# HA_Power.net
KiCad netlist of a schematic drawn in Altium Designer
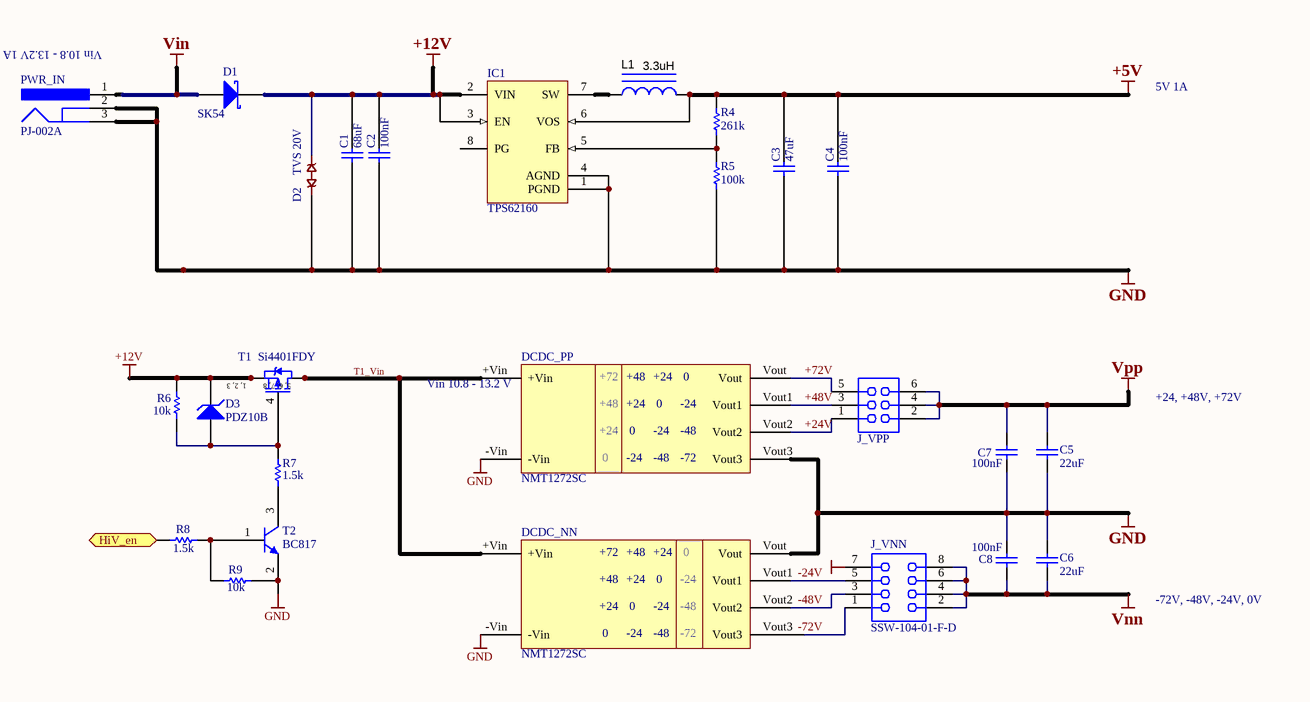
[diagram p0: HA_Power.SchDoc]

(export (version "E")
  (design (tool "Eeschema 10.0.6"))
  (components
    (comp (ref "C1")
      (value "68uF")
      (footprint "MURA-GRM-55D_V")
      (fields (field (name "MPN") "KRM55WR71E686MH01L") (field (name "MANUFACTURER") "Murata"))
      (libsource (lib "Altium Content Vault") (part "CMP-0817-00001-1"))
    )
    (comp (ref "C2")
      (value "100nF")
      (footprint "CAPC0805(2012)75_N")
      (fields (field (name "TOLERANCE") "±10%"))
      (libsource (lib "Altium Content Vault") (part "CMP-1036-00417-1"))
    )
    (comp (ref "C3")
      (value "47uF")
      (footprint "CAPC0805(2012)75_N")
      (fields (field (name "TOLERANCE") "±10%") (field (name "PARTNUMBER") "GRM21BR61A476ME15L"))
      (libsource (lib "Altium Content Vault") (part "CMP-1036-00417-1"))
    )
    (comp (ref "C4")
      (value "100nF")
      (footprint "CAPC0805(2012)75_N")
      (fields (field (name "TOLERANCE") "±10%"))
      (libsource (lib "Altium Content Vault") (part "CMP-1036-00417-1"))
    )
    (comp (ref "C5")
      (value "22uF")
      (footprint "MURA-GRM-55D_V")
      (fields (field (name "MPN") "KRM55WR72A226MH01L") (field (name "MANUFACTURER") "Murata"))
      (libsource (lib "Altium Content Vault") (part "CMP-0817-00001-1"))
    )
    (comp (ref "C6")
      (value "22uF")
      (footprint "MURA-GRM-55D_V")
      (fields (field (name "MPN") "KRM55WR72A226MH01L") (field (name "MANUFACTURER") "Murata"))
      (libsource (lib "Altium Content Vault") (part "CMP-0817-00001-1"))
    )
    (comp (ref "C7")
      (value "100nF")
      (footprint "CAPC0805(2012)75_N")
      (fields (field (name "TOLERANCE") "±10%"))
      (libsource (lib "Altium Content Vault") (part "CMP-1036-00417-1"))
    )
    (comp (ref "C8")
      (value "100nF")
      (footprint "CAPC0805(2012)75_N")
      (fields (field (name "TOLERANCE") "±10%"))
      (libsource (lib "Altium Content Vault") (part "CMP-1036-00417-1"))
    )
    (comp (ref "D1")
      (value "SK54")
      (footprint "VISH-DO-214AC-2_V")
      (fields (field (name "MANUFACTURER") "Micro commercial co") (field (name "MPN") "SK54A-LTP"))
      (libsource (lib "Altium Content Vault") (part "CMP-0549-00004-1"))
    )
    (comp (ref "D2")
      (value "TVS 20V")
      (footprint "DO214AC_BIDIR")
      (fields (field (name "MANUFACTURER") "Bourns") (field (name "MPN") "SMAJ20CA"))
      (libsource (lib "mms") (part "DIODE_BIDIR-DO214AC"))
    )
    (comp (ref "D3")
      (value "PDZ10B")
      (footprint "NXP-SOD323_V")
      (description "Zener diode")
      (fields (field (name "MANUFACTURER") "NXP"))
      (libsource (lib "Altium Content Vault") (part "CMP-2000-06888-1"))
    )
    (comp (ref "DCDC_NN")
      (value "NMT1272SC")
      (footprint "NMT1272SC")
      (fields (field (name "MANUFACTURER") "Murata"))
      (libsource (lib "Lib_murata") (part "NMT1272SC"))
    )
    (comp (ref "DCDC_PP")
      (value "NMT1272SC")
      (footprint "NMT1272SC")
      (fields (field (name "MANUFACTURER") "Murata"))
      (libsource (lib "Lib_murata") (part "NMT1272SC"))
    )
    (comp (ref "IC1")
      (value "TPS62160")
      (footprint "DGK8_N")
      (fields (field (name "MANUFACTURER") "Texas Instruments") (field (name "MPN") "TPS62160DGKR"))
      (libsource (lib "Altium Content Vault") (part "CMP-0323-00440-1"))
    )
    (comp (ref "J_VNN")
      (value "SSW-104-01-F-D")
      (footprint "SMTC-SSW-104-01-X-D")
      (description "SQ Post Socket, Through-hole, Vertical, -55 to 125 degC, 2.54mm Pitch, 8-Pin, Female, RoHS")
      (fields (field (name "MANUFACTURER") "Samtec"))
      (libsource (lib "Altium Content Vault") (part "CMP-1023-00336-1"))
    )
    (comp (ref "J_VPP")
      (value "SSW-103-01-F-D")
      (footprint "SMTC-SSW-103-01-X-D")
      (description "SQ Post Socket, Through-hole, Vertical, -55 to 125 degC, 2.54 mm Pitch, 6-Pin, Female, RoHS")
      (fields (field (name "MANUFACTURER") "Samtec"))
      (libsource (lib "Altium Content Vault") (part "CMP-1023-00329-1"))
    )
    (comp (ref "L1")
      (value "3.3uH")
      (footprint "XPL2010")
      (description "XPL2010 Inductor")
      (fields (field (name "MPN") "XPL2010-332MLB") (field (name "MANUFACTURER") "Coilcraft"))
      (libsource (lib "Inductor_Coilcraft") (part "XPL2010-332MLB"))
    )
    (comp (ref "PWR_IN")
      (value "PJ-002A")
      (footprint "CUI-PJ-002A_V")
      (fields (field (name "MANUFACTURER") "CUIInc."))
      (libsource (lib "Altium Content Vault") (part "CMP-2000-06895-1"))
    )
    (comp (ref "R4")
      (value "261k")
      (footprint "RESC0805(2012)_L")
      (description "0.125W 1% 0805 (2012 Metric)  SMD")
      (fields (field (name "POWER") "0.125 W") (field (name "TOLERANCE") "1 %"))
      (libsource (lib "Altium Content Vault") (part "CMP-1013-00429-1"))
    )
    (comp (ref "R5")
      (value "100k")
      (footprint "RESC0805(2012)_L")
      (description "0.125W 1% 0805 (2012 Metric)  SMD")
      (fields (field (name "POWER") "0.125 W") (field (name "TOLERANCE") "1 %"))
      (libsource (lib "Altium Content Vault") (part "CMP-1013-00429-1"))
    )
    (comp (ref "R6")
      (value "10k")
      (footprint "RESC0805(2012)_L")
      (description "0.125W 1% 0805 (2012 Metric)  SMD")
      (fields (field (name "POWER") "0.125 W") (field (name "TOLERANCE") "1 %"))
      (libsource (lib "Altium Content Vault") (part "CMP-1013-00429-1"))
    )
    (comp (ref "R7")
      (value "1.5k")
      (footprint "RESC0805(2012)_L")
      (description "0.125W 1% 0805 (2012 Metric)  SMD")
      (fields (field (name "POWER") "0.125 W") (field (name "TOLERANCE") "1 %"))
      (libsource (lib "Altium Content Vault") (part "CMP-1013-00429-1"))
    )
    (comp (ref "R8")
      (value "1.5k")
      (footprint "RESC0805(2012)_L")
      (description "0.125W 1% 0805 (2012 Metric)  SMD")
      (fields (field (name "POWER") "0.125 W") (field (name "TOLERANCE") "1 %"))
      (libsource (lib "Altium Content Vault") (part "CMP-1013-00429-1"))
    )
    (comp (ref "R9")
      (value "10k")
      (footprint "RESC0805(2012)_L")
      (description "0.125W 1% 0805 (2012 Metric)  SMD")
      (fields (field (name "POWER") "0.125 W") (field (name "TOLERANCE") "1 %"))
      (libsource (lib "Altium Content Vault") (part "CMP-1013-00429-1"))
    )
    (comp (ref "T1")
      (value "Si4401FDY")
      (footprint "SO08")
      (description "HEXFET Power MOSFET")
      (libsource (lib "fb") (part "P-MOSFET2"))
    )
    (comp (ref "T2")
      (value "BC817")
      (footprint "DIOD-SOT323-3_V")
      (description "NPN Small Signal Transistor, 45 V, 500 mA")
      (fields (field (name "MANUFACTURER") "DiodesIncorporated") (field (name "MPN") "BC817-40W-7"))
      (libsource (lib "Altium Content Vault") (part "CMP-2000-05934-1"))
    )
  )
  (nets
    (net (code "1") (name "+5V") (class "Default")
      (node (ref "C3") (pin "2") (pinfunction "2_2") (pintype "passive"))
      (node (ref "C4") (pin "2") (pinfunction "2_2") (pintype "passive"))
      (node (ref "IC1") (pin "6") (pinfunction "VOS_6") (pintype "input"))
      (node (ref "L1") (pin "2") (pinfunction "2_2") (pintype "passive"))
      (node (ref "R4") (pin "1") (pinfunction "1_1") (pintype "passive"))
    )
    (net (code "2") (name "+12V") (class "Default")
      (node (ref "C1") (pin "2") (pinfunction "2_2") (pintype "passive"))
      (node (ref "C2") (pin "2") (pinfunction "2_2") (pintype "passive"))
      (node (ref "D1") (pin "2") (pinfunction "K_2") (pintype "passive"))
      (node (ref "D2") (pin "2") (pinfunction "2_2") (pintype "passive"))
      (node (ref "D3") (pin "2") (pinfunction "K_2") (pintype "passive"))
      (node (ref "IC1") (pin "2") (pinfunction "VIN_2") (pintype "power_in"))
      (node (ref "IC1") (pin "3") (pinfunction "EN_3") (pintype "input"))
      (node (ref "R6") (pin "1") (pinfunction "1_1") (pintype "passive"))
      (node (ref "T1") (pin "1") (pinfunction "S_1") (pintype "passive"))
      (node (ref "T1") (pin "2") (pinfunction "S_2") (pintype "passive"))
      (node (ref "T1") (pin "3") (pinfunction "S_3") (pintype "passive"))
    )
    (net (code "3") (name "/+24V") (class "Default")
      (node (ref "DCDC_PP") (pin "Vout2") (pinfunction "Vout2_Vout2") (pintype "passive"))
      (node (ref "J_VPP") (pin "1") (pinfunction "1_1") (pintype "passive"))
    )
    (net (code "4") (name "/+48V") (class "Default")
      (node (ref "DCDC_PP") (pin "Vout1") (pinfunction "Vout1_Vout1") (pintype "passive"))
      (node (ref "J_VPP") (pin "3") (pinfunction "3_3") (pintype "passive"))
    )
    (net (code "5") (name "/+72V") (class "Default")
      (node (ref "DCDC_PP") (pin "Vout") (pinfunction "Vout_Vout") (pintype "passive"))
      (node (ref "J_VPP") (pin "5") (pinfunction "5_5") (pintype "passive"))
    )
    (net (code "6") (name "/-24V") (class "Default")
      (node (ref "DCDC_NN") (pin "Vout1") (pinfunction "Vout1_Vout1") (pintype "passive"))
      (node (ref "J_VNN") (pin "5") (pinfunction "5_5") (pintype "passive"))
    )
    (net (code "7") (name "/-48V") (class "Default")
      (node (ref "DCDC_NN") (pin "Vout2") (pinfunction "Vout2_Vout2") (pintype "passive"))
      (node (ref "J_VNN") (pin "3") (pinfunction "3_3") (pintype "passive"))
    )
    (net (code "8") (name "/-72V") (class "Default")
      (node (ref "DCDC_NN") (pin "Vout3") (pinfunction "Vout3_Vout3") (pintype "passive"))
      (node (ref "J_VNN") (pin "1") (pinfunction "1_1") (pintype "passive"))
    )
    (net (code "9") (name "/HiV_en") (class "Default")
      (node (ref "R8") (pin "2") (pinfunction "2_2") (pintype "passive"))
    )
    (net (code "10") (name "/T1_Vin") (class "Default")
      (node (ref "DCDC_NN") (pin "+Vin") (pinfunction "+Vin_+Vin") (pintype "power_in"))
      (node (ref "DCDC_PP") (pin "+Vin") (pinfunction "+Vin_+Vin") (pintype "power_in"))
      (node (ref "T1") (pin "5") (pinfunction "D_5") (pintype "passive"))
      (node (ref "T1") (pin "6") (pinfunction "D_6") (pintype "passive"))
      (node (ref "T1") (pin "7") (pinfunction "D_7") (pintype "passive"))
      (node (ref "T1") (pin "8") (pinfunction "D_8") (pintype "passive"))
    )
    (net (code "11") (name "GND") (class "Default")
      (node (ref "C1") (pin "1") (pinfunction "1_1") (pintype "passive"))
      (node (ref "C2") (pin "1") (pinfunction "1_1") (pintype "passive"))
      (node (ref "C3") (pin "1") (pinfunction "1_1") (pintype "passive"))
      (node (ref "C4") (pin "1") (pinfunction "1_1") (pintype "passive"))
      (node (ref "C5") (pin "1") (pinfunction "1_1") (pintype "passive"))
      (node (ref "C6") (pin "2") (pinfunction "2_2") (pintype "passive"))
      (node (ref "C7") (pin "1") (pinfunction "1_1") (pintype "passive"))
      (node (ref "C8") (pin "2") (pinfunction "2_2") (pintype "passive"))
      (node (ref "D2") (pin "1") (pinfunction "1_1") (pintype "passive"))
      (node (ref "DCDC_NN") (pin "-Vin") (pinfunction "-Vin_-Vin") (pintype "passive"))
      (node (ref "DCDC_NN") (pin "Vout") (pinfunction "Vout_Vout") (pintype "passive"))
      (node (ref "DCDC_PP") (pin "-Vin") (pinfunction "-Vin_-Vin") (pintype "passive"))
      (node (ref "DCDC_PP") (pin "Vout3") (pinfunction "Vout3_Vout3") (pintype "passive"))
      (node (ref "IC1") (pin "1") (pinfunction "PGND_1") (pintype "power_in"))
      (node (ref "IC1") (pin "4") (pinfunction "AGND_4") (pintype "power_in"))
      (node (ref "J_VNN") (pin "7") (pinfunction "7_7") (pintype "passive"))
      (node (ref "PWR_IN") (pin "2") (pinfunction "2_2") (pintype "passive"))
      (node (ref "PWR_IN") (pin "3") (pinfunction "3_3") (pintype "passive"))
      (node (ref "R5") (pin "2") (pinfunction "2_2") (pintype "passive"))
      (node (ref "R9") (pin "1") (pinfunction "1_1") (pintype "passive"))
      (node (ref "T2") (pin "2") (pinfunction "E_2") (pintype "passive"))
    )
    (net (code "12") (name "Net-(D3-A)") (class "Default")
      (node (ref "D3") (pin "1") (pinfunction "A_1") (pintype "passive"))
      (node (ref "R6") (pin "2") (pinfunction "2_2") (pintype "passive"))
      (node (ref "R7") (pin "2") (pinfunction "2_2") (pintype "passive"))
      (node (ref "T1") (pin "4") (pinfunction "G_4") (pintype "passive"))
    )
    (net (code "13") (name "Net-(IC1-FB)") (class "Default")
      (node (ref "IC1") (pin "5") (pinfunction "FB_5") (pintype "input"))
      (node (ref "R4") (pin "2") (pinfunction "2_2") (pintype "passive"))
      (node (ref "R5") (pin "1") (pinfunction "1_1") (pintype "passive"))
    )
    (net (code "14") (name "Net-(IC1-SW)") (class "Default")
      (node (ref "IC1") (pin "7") (pinfunction "SW_7") (pintype "power_in"))
      (node (ref "L1") (pin "1") (pinfunction "1_1") (pintype "passive"))
    )
    (net (code "15") (name "Net-(T2-B)") (class "Default")
      (node (ref "R8") (pin "1") (pinfunction "1_1") (pintype "passive"))
      (node (ref "R9") (pin "2") (pinfunction "2_2") (pintype "passive"))
      (node (ref "T2") (pin "1") (pinfunction "B_1") (pintype "passive"))
    )
    (net (code "16") (name "Net-(T2-C)") (class "Default")
      (node (ref "R7") (pin "1") (pinfunction "1_1") (pintype "passive"))
      (node (ref "T2") (pin "3") (pinfunction "C_3") (pintype "passive"))
    )
    (net (code "17") (name "Vin") (class "Default")
      (node (ref "D1") (pin "1") (pinfunction "A_1") (pintype "passive"))
      (node (ref "PWR_IN") (pin "1") (pinfunction "1_1") (pintype "passive"))
    )
    (net (code "18") (name "Vnn") (class "Default")
      (node (ref "C6") (pin "1") (pinfunction "1_1") (pintype "passive"))
      (node (ref "C8") (pin "1") (pinfunction "1_1") (pintype "passive"))
      (node (ref "J_VNN") (pin "2") (pinfunction "2_2") (pintype "passive"))
      (node (ref "J_VNN") (pin "4") (pinfunction "4_4") (pintype "passive"))
      (node (ref "J_VNN") (pin "6") (pinfunction "6_6") (pintype "passive"))
      (node (ref "J_VNN") (pin "8") (pinfunction "8_8") (pintype "passive"))
    )
    (net (code "19") (name "Vpp") (class "Default")
      (node (ref "C5") (pin "2") (pinfunction "2_2") (pintype "passive"))
      (node (ref "C7") (pin "2") (pinfunction "2_2") (pintype "passive"))
      (node (ref "J_VPP") (pin "2") (pinfunction "2_2") (pintype "passive"))
      (node (ref "J_VPP") (pin "4") (pinfunction "4_4") (pintype "passive"))
      (node (ref "J_VPP") (pin "6") (pinfunction "6_6") (pintype "passive"))
    )
    (net (code "20") (name "unconnected-(IC1-PG-Pad8)") (class "Default")
      (node (ref "IC1") (pin "8") (pinfunction "PG_8") (pintype "tri_state"))
    )
  )
)
